# uson_wson_breakout.net
KiCad netlist of a schematic drawn in EAGLE
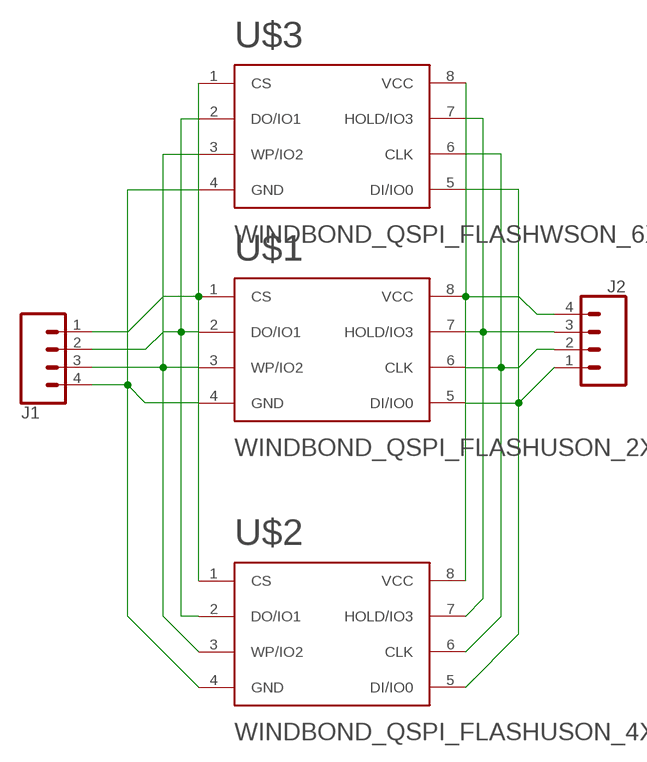
[diagram p0: schematic, sheet 1]

(export (version "E")
  (design (tool "Eeschema 10.0.6"))
  (components
    (comp (ref "J1")
      (value "CONN_041X04_NO_SILK")
      (footprint "eagle-import:1X04_NO_SILK")
      (libsource (lib "eagle-import") (part "CONN_041X04_NO_SILK"))
    )
    (comp (ref "J2")
      (value "CONN_041X04_NO_SILK")
      (footprint "eagle-import:1X04_NO_SILK")
      (libsource (lib "eagle-import") (part "CONN_041X04_NO_SILK"))
    )
    (comp (ref "U$1")
      (value "WINDBOND_QSPI_FLASHUSON_2X3")
      (footprint "eagle-import:USON_2X3MM")
      (libsource (lib "eagle-import") (part "WINDBOND_QSPI_FLASHUSON_2X3"))
    )
    (comp (ref "U$2")
      (value "WINDBOND_QSPI_FLASHUSON_4X3")
      (footprint "eagle-import:USON_4X3MM")
      (libsource (lib "eagle-import") (part "WINDBOND_QSPI_FLASHUSON_4X3"))
    )
    (comp (ref "U$3")
      (value "WINDBOND_QSPI_FLASHWSON_6X5")
      (footprint "eagle-import:WSON_6X5MM")
      (libsource (lib "eagle-import") (part "WINDBOND_QSPI_FLASHWSON_6X5"))
    )
  )
  (nets
    (net (code "1") (name "Net-(U$1-CLK)") (class "Default")
      (node (ref "J2") (pin "2") (pinfunction "2_2") (pintype "passive"))
      (node (ref "U$1") (pin "6") (pinfunction "CLK_6") (pintype "bidirectional"))
      (node (ref "U$2") (pin "6") (pinfunction "CLK_6") (pintype "bidirectional"))
      (node (ref "U$3") (pin "6") (pinfunction "CLK_6") (pintype "bidirectional"))
    )
    (net (code "2") (name "Net-(U$1-CS)") (class "Default")
      (node (ref "J1") (pin "1") (pinfunction "1_1") (pintype "passive"))
      (node (ref "U$1") (pin "1") (pinfunction "CS_1") (pintype "bidirectional"))
      (node (ref "U$2") (pin "1") (pinfunction "CS_1") (pintype "bidirectional"))
      (node (ref "U$3") (pin "1") (pinfunction "CS_1") (pintype "bidirectional"))
    )
    (net (code "3") (name "Net-(U$1-DI{slash}IO0)") (class "Default")
      (node (ref "J2") (pin "1") (pinfunction "1_1") (pintype "passive"))
      (node (ref "U$1") (pin "5") (pinfunction "DI/IO0_5") (pintype "bidirectional"))
      (node (ref "U$2") (pin "5") (pinfunction "DI/IO0_5") (pintype "bidirectional"))
      (node (ref "U$3") (pin "5") (pinfunction "DI/IO0_5") (pintype "bidirectional"))
    )
    (net (code "4") (name "Net-(U$1-DO{slash}IO1)") (class "Default")
      (node (ref "J1") (pin "2") (pinfunction "2_2") (pintype "passive"))
      (node (ref "U$1") (pin "2") (pinfunction "DO/IO1_2") (pintype "bidirectional"))
      (node (ref "U$2") (pin "2") (pinfunction "DO/IO1_2") (pintype "bidirectional"))
      (node (ref "U$3") (pin "2") (pinfunction "DO/IO1_2") (pintype "bidirectional"))
    )
    (net (code "5") (name "Net-(U$1-GND)") (class "Default")
      (node (ref "J1") (pin "4") (pinfunction "4_4") (pintype "passive"))
      (node (ref "U$1") (pin "4") (pinfunction "GND_4") (pintype "power_in"))
      (node (ref "U$2") (pin "4") (pinfunction "GND_4") (pintype "power_in"))
      (node (ref "U$3") (pin "4") (pinfunction "GND_4") (pintype "power_in"))
    )
    (net (code "6") (name "Net-(U$1-HOLD{slash}IO3)") (class "Default")
      (node (ref "J2") (pin "3") (pinfunction "3_3") (pintype "passive"))
      (node (ref "U$1") (pin "7") (pinfunction "HOLD/IO3_7") (pintype "bidirectional"))
      (node (ref "U$2") (pin "7") (pinfunction "HOLD/IO3_7") (pintype "bidirectional"))
      (node (ref "U$3") (pin "7") (pinfunction "HOLD/IO3_7") (pintype "bidirectional"))
    )
    (net (code "7") (name "Net-(U$1-VCC)") (class "Default")
      (node (ref "J2") (pin "4") (pinfunction "4_4") (pintype "passive"))
      (node (ref "U$1") (pin "8") (pinfunction "VCC_8") (pintype "passive"))
      (node (ref "U$2") (pin "8") (pinfunction "VCC_8") (pintype "passive"))
      (node (ref "U$3") (pin "8") (pinfunction "VCC_8") (pintype "passive"))
    )
    (net (code "8") (name "Net-(U$1-WP{slash}IO2)") (class "Default")
      (node (ref "J1") (pin "3") (pinfunction "3_3") (pintype "passive"))
      (node (ref "U$1") (pin "3") (pinfunction "WP/IO2_3") (pintype "bidirectional"))
      (node (ref "U$2") (pin "3") (pinfunction "WP/IO2_3") (pintype "bidirectional"))
      (node (ref "U$3") (pin "3") (pinfunction "WP/IO2_3") (pintype "bidirectional"))
    )
  )
)
